# ppcb.net
KiCad netlist of a schematic drawn in EAGLE
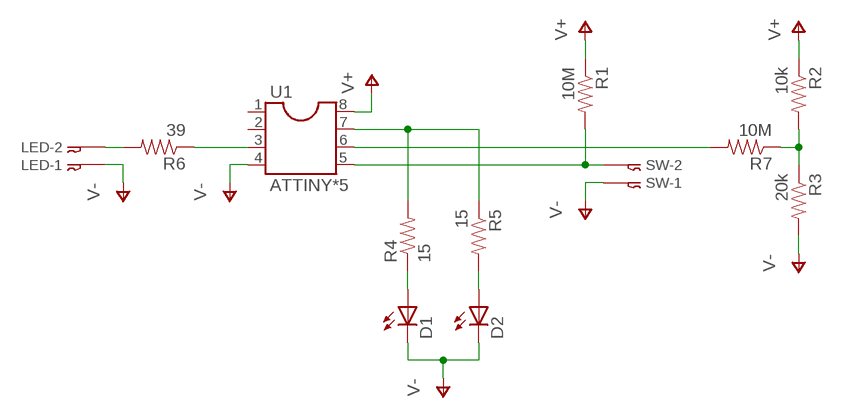
[diagram p0: schematic, sheet 1]

(export (version "E")
  (design (tool "Eeschema 10.0.6"))
  (components
    (comp (ref "D1")
      (value "LED5MM")
      (footprint "eagle-import:LED5MM")
      (libsource (lib "eagle-import") (part "LED5MM"))
    )
    (comp (ref "D2")
      (value "LED5MM")
      (footprint "eagle-import:LED5MM")
      (libsource (lib "eagle-import") (part "LED5MM"))
    )
    (comp (ref "LED")
      (value "02-JST")
      (footprint "eagle-import:B2B-XH")
      (libsource (lib "eagle-import") (part "02-JST"))
    )
    (comp (ref "R1")
      (value "10M")
      (footprint "eagle-import:AXIAL-0.4")
      (libsource (lib "eagle-import") (part "RESISTORPTH-1/4W"))
    )
    (comp (ref "R2")
      (value "10k")
      (footprint "eagle-import:AXIAL-0.4")
      (libsource (lib "eagle-import") (part "RESISTORPTH-1/4W"))
    )
    (comp (ref "R3")
      (value "20k")
      (footprint "eagle-import:AXIAL-0.4")
      (libsource (lib "eagle-import") (part "RESISTORPTH-1/4W"))
    )
    (comp (ref "R4")
      (value "15")
      (footprint "eagle-import:AXIAL-0.4")
      (libsource (lib "eagle-import") (part "RESISTORPTH-1/4W"))
    )
    (comp (ref "R5")
      (value "15")
      (footprint "eagle-import:AXIAL-0.4")
      (libsource (lib "eagle-import") (part "RESISTORPTH-1/4W"))
    )
    (comp (ref "R6")
      (value "39")
      (footprint "eagle-import:AXIAL-0.4")
      (libsource (lib "eagle-import") (part "RESISTORPTH-1/4W"))
    )
    (comp (ref "R7")
      (value "10M")
      (footprint "eagle-import:AXIAL-0.4")
      (libsource (lib "eagle-import") (part "RESISTORPTH-1/4W"))
    )
    (comp (ref "SW")
      (value "02-JST")
      (footprint "eagle-import:B2B-XH")
      (libsource (lib "eagle-import") (part "02-JST"))
    )
    (comp (ref "U1")
      (value "ATTINY*5")
      (footprint "eagle-import:SOCKET-08")
      (libsource (lib "eagle-import") (part "DIL8S"))
    )
  )
  (nets
    (net (code "1") (name "Net-(LEDB-1)") (class "Default")
      (node (ref "LED") (pin "P$2") (pinfunction "1_P$2") (pintype "passive"))
      (node (ref "R6") (pin "P$2") (pinfunction "2_P$2") (pintype "passive"))
    )
    (net (code "2") (name "Net-(R1-2)") (class "Default")
      (node (ref "R1") (pin "P$2") (pinfunction "2_P$2") (pintype "passive"))
      (node (ref "SW") (pin "P$2") (pinfunction "1_P$2") (pintype "passive"))
      (node (ref "U1") (pin "5") (pinfunction "5_5") (pintype "passive"))
    )
    (net (code "3") (name "Net-(R2-2)") (class "Default")
      (node (ref "R2") (pin "P$2") (pinfunction "2_P$2") (pintype "passive"))
      (node (ref "R3") (pin "P$1") (pinfunction "1_P$1") (pintype "passive"))
      (node (ref "R7") (pin "P$1") (pinfunction "1_P$1") (pintype "passive"))
    )
    (net (code "4") (name "Net-(R4-1)") (class "Default")
      (node (ref "D1") (pin "A") (pinfunction "A_A") (pintype "passive"))
      (node (ref "R4") (pin "P$1") (pinfunction "1_P$1") (pintype "passive"))
    )
    (net (code "5") (name "Net-(R4-2)") (class "Default")
      (node (ref "R4") (pin "P$2") (pinfunction "2_P$2") (pintype "passive"))
      (node (ref "R5") (pin "P$1") (pinfunction "1_P$1") (pintype "passive"))
      (node (ref "U1") (pin "7") (pinfunction "7_7") (pintype "passive"))
    )
    (net (code "6") (name "Net-(R5-2)") (class "Default")
      (node (ref "D2") (pin "A") (pinfunction "A_A") (pintype "passive"))
      (node (ref "R5") (pin "P$2") (pinfunction "2_P$2") (pintype "passive"))
    )
    (net (code "7") (name "Net-(R6-1)") (class "Default")
      (node (ref "R6") (pin "P$1") (pinfunction "1_P$1") (pintype "passive"))
      (node (ref "U1") (pin "3") (pinfunction "3_3") (pintype "passive"))
    )
    (net (code "8") (name "Net-(R7-2)") (class "Default")
      (node (ref "R7") (pin "P$2") (pinfunction "2_P$2") (pintype "passive"))
      (node (ref "U1") (pin "6") (pinfunction "6_6") (pintype "passive"))
    )
    (net (code "9") (name "V+") (class "Default")
      (node (ref "R1") (pin "P$1") (pinfunction "1_P$1") (pintype "passive"))
      (node (ref "R2") (pin "P$1") (pinfunction "1_P$1") (pintype "passive"))
      (node (ref "U1") (pin "8") (pinfunction "8_8") (pintype "passive"))
    )
    (net (code "10") (name "V-") (class "Default")
      (node (ref "D1") (pin "K") (pinfunction "C_K") (pintype "passive"))
      (node (ref "D2") (pin "K") (pinfunction "C_K") (pintype "passive"))
      (node (ref "LED") (pin "P$1") (pinfunction "1_P$1") (pintype "passive"))
      (node (ref "R3") (pin "P$2") (pinfunction "2_P$2") (pintype "passive"))
      (node (ref "SW") (pin "P$1") (pinfunction "1_P$1") (pintype "passive"))
      (node (ref "U1") (pin "4") (pinfunction "4_4") (pintype "passive"))
    )
    (net (code "11") (name "unconnected-(U1-Pad1)") (class "Default")
      (node (ref "U1") (pin "1") (pinfunction "1_1") (pintype "passive"))
    )
    (net (code "12") (name "unconnected-(U1-Pad2)") (class "Default")
      (node (ref "U1") (pin "2") (pinfunction "2_2") (pintype "passive"))
    )
  )
)
